# esp32.net
KiCad netlist of a schematic drawn in Altium Designer
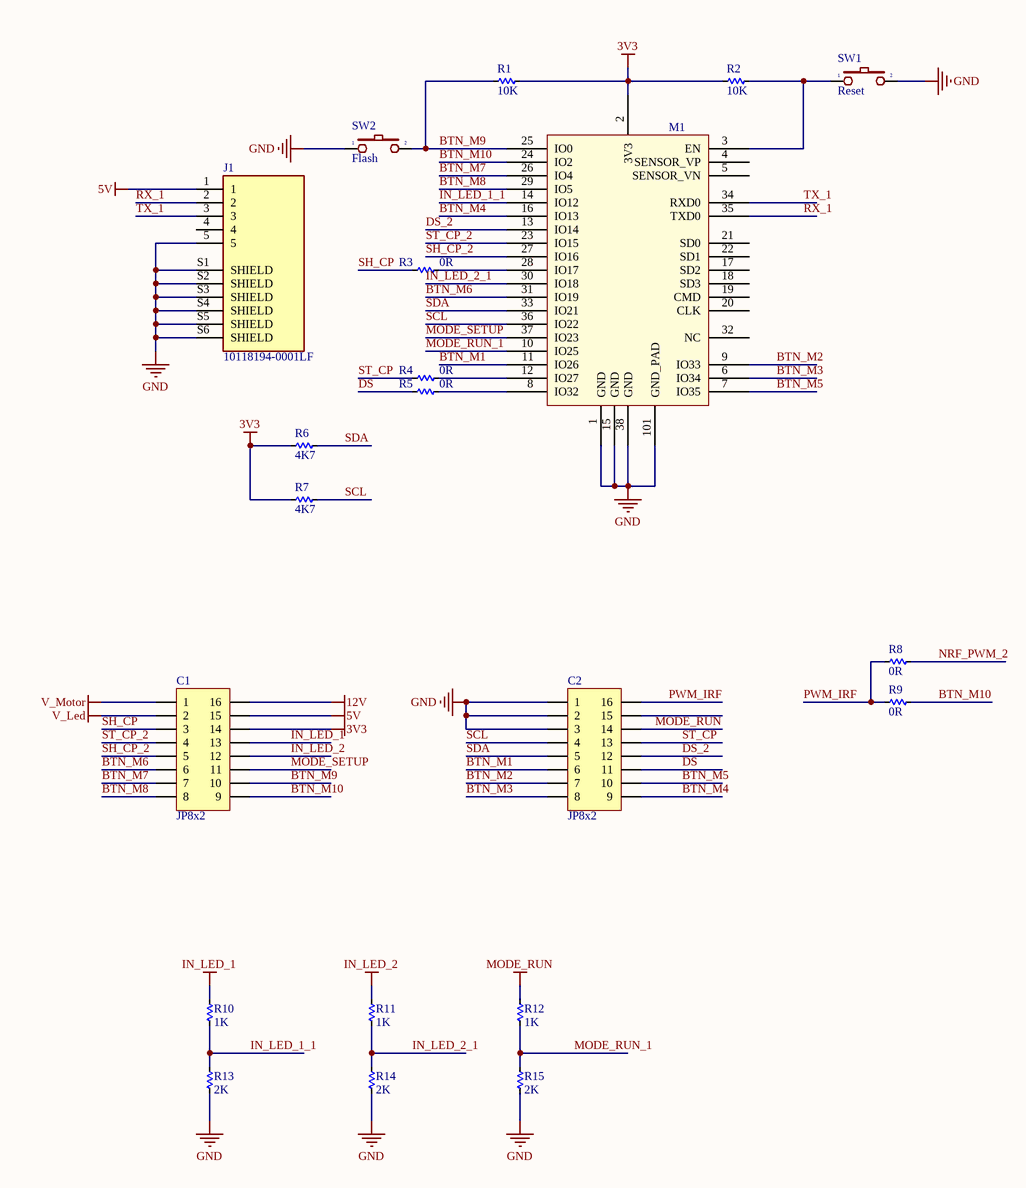
[diagram p0: esp32.SchDoc]

(export (version "E")
  (design (tool "Eeschema 10.0.6"))
  (components
    (comp (ref "C1")
      (value "JP8x2")
      (footprint "JP8-C2T")
      (description "WR-PHD 2.54 mm Dual Socket Header")
      (fields
        (field (name "MANUFACTURER") "Würth Elektronik eiSos GmbH")
        (field (name "PARTNO") "61301621821")
        (field (name "CREATED BY") "Karrer Zheng")
      )
      (libsource (lib "LIBRARY") (part "JP8x2"))
    )
    (comp (ref "C2")
      (value "JP8x2")
      (footprint "JP8-C2T")
      (description "WR-PHD 2.54 mm Dual Socket Header")
      (fields
        (field (name "MANUFACTURER") "Würth Elektronik eiSos GmbH")
        (field (name "PARTNO") "61301621821")
        (field (name "CREATED BY") "Karrer Zheng")
      )
      (libsource (lib "LIBRARY") (part "JP8x2"))
    )
    (comp (ref "J1")
      (value "10118194-0001LF")
      (footprint "AMPHENOL_10118194-0001LF")
      (description "USB - micro B USB 2.0 Receptacle Connector 5 Position Surface Mount, Right Angle; Through Hole")
      (fields (field (name "MF") "Amphenol ICC"))
      (libsource (lib "10118194-0001LF") (part "10118194-0001LF"))
    )
    (comp (ref "M1")
      (value "ESP32S_Module")
      (footprint "ESP32S")
      (description "Esp-32S")
      (libsource (lib "ESP32S") (part "ESP32S_Module"))
    )
    (comp (ref "R1")
      (value "10K")
      (footprint "RES-SMD-0603")
      (description "Resistor")
      (fields
        (field (name "MANUFACTURER") "Generic Components")
        (field (name "PUBLISHER") "Altium Hobart Technology Centre")
      )
      (libsource (lib "LIBRARY") (part "Res-SMD"))
    )
    (comp (ref "R2")
      (value "10K")
      (footprint "RES-SMD-0603")
      (description "Resistor")
      (fields
        (field (name "MANUFACTURER") "Generic Components")
        (field (name "PUBLISHER") "Altium Hobart Technology Centre")
      )
      (libsource (lib "LIBRARY") (part "Res-SMD"))
    )
    (comp (ref "R3")
      (value "0R")
      (footprint "RES-SMD-0603")
      (description "Resistor")
      (fields
        (field (name "MANUFACTURER") "Generic Components")
        (field (name "PUBLISHER") "Altium Hobart Technology Centre")
      )
      (libsource (lib "LIBRARY") (part "Res-SMD"))
    )
    (comp (ref "R4")
      (value "0R")
      (footprint "RES-SMD-0603")
      (description "Resistor")
      (fields
        (field (name "MANUFACTURER") "Generic Components")
        (field (name "PUBLISHER") "Altium Hobart Technology Centre")
      )
      (libsource (lib "LIBRARY") (part "Res-SMD"))
    )
    (comp (ref "R5")
      (value "0R")
      (footprint "RES-SMD-0603")
      (description "Resistor")
      (fields
        (field (name "MANUFACTURER") "Generic Components")
        (field (name "PUBLISHER") "Altium Hobart Technology Centre")
      )
      (libsource (lib "LIBRARY") (part "Res-SMD"))
    )
    (comp (ref "R6")
      (value "4K7")
      (footprint "RES-SMD-0603")
      (description "Resistor")
      (fields
        (field (name "MANUFACTURER") "Generic Components")
        (field (name "PUBLISHER") "Altium Hobart Technology Centre")
      )
      (libsource (lib "LIBRARY") (part "Res-SMD"))
    )
    (comp (ref "R7")
      (value "4K7")
      (footprint "RES-SMD-0603")
      (description "Resistor")
      (fields
        (field (name "MANUFACTURER") "Generic Components")
        (field (name "PUBLISHER") "Altium Hobart Technology Centre")
      )
      (libsource (lib "LIBRARY") (part "Res-SMD"))
    )
    (comp (ref "R8")
      (value "0R")
      (footprint "RES-SMD-0603")
      (description "Resistor")
      (fields
        (field (name "MANUFACTURER") "Generic Components")
        (field (name "PUBLISHER") "Altium Hobart Technology Centre")
      )
      (libsource (lib "LIBRARY") (part "Res-SMD"))
    )
    (comp (ref "R9")
      (value "0R")
      (footprint "RES-SMD-0603")
      (description "Resistor")
      (fields
        (field (name "MANUFACTURER") "Generic Components")
        (field (name "PUBLISHER") "Altium Hobart Technology Centre")
      )
      (libsource (lib "LIBRARY") (part "Res-SMD"))
    )
    (comp (ref "R10")
      (value "1K")
      (footprint "RES-SMD-0603")
      (description "Resistor")
      (fields
        (field (name "MANUFACTURER") "Generic Components")
        (field (name "PUBLISHER") "Altium Hobart Technology Centre")
      )
      (libsource (lib "LIBRARY") (part "Res-SMD"))
    )
    (comp (ref "R11")
      (value "1K")
      (footprint "RES-SMD-0603")
      (description "Resistor")
      (fields
        (field (name "MANUFACTURER") "Generic Components")
        (field (name "PUBLISHER") "Altium Hobart Technology Centre")
      )
      (libsource (lib "LIBRARY") (part "Res-SMD"))
    )
    (comp (ref "R12")
      (value "1K")
      (footprint "RES-SMD-0603")
      (description "Resistor")
      (fields
        (field (name "MANUFACTURER") "Generic Components")
        (field (name "PUBLISHER") "Altium Hobart Technology Centre")
      )
      (libsource (lib "LIBRARY") (part "Res-SMD"))
    )
    (comp (ref "R13")
      (value "2K")
      (footprint "RES-SMD-0603")
      (description "Resistor")
      (fields
        (field (name "MANUFACTURER") "Generic Components")
        (field (name "PUBLISHER") "Altium Hobart Technology Centre")
      )
      (libsource (lib "LIBRARY") (part "Res-SMD"))
    )
    (comp (ref "R14")
      (value "2K")
      (footprint "RES-SMD-0603")
      (description "Resistor")
      (fields
        (field (name "MANUFACTURER") "Generic Components")
        (field (name "PUBLISHER") "Altium Hobart Technology Centre")
      )
      (libsource (lib "LIBRARY") (part "Res-SMD"))
    )
    (comp (ref "R15")
      (value "2K")
      (footprint "RES-SMD-0603")
      (description "Resistor")
      (fields
        (field (name "MANUFACTURER") "Generic Components")
        (field (name "PUBLISHER") "Altium Hobart Technology Centre")
      )
      (libsource (lib "LIBRARY") (part "Res-SMD"))
    )
    (comp (ref "SW1")
      (value "Reset")
      (footprint "SW1-SMD")
      (description "Switch button 2 pin")
      (libsource (lib "LIBRARY") (part "SW2"))
    )
    (comp (ref "SW2")
      (value "Flash")
      (footprint "SW-DIP1-1")
      (description "Switch button 2 pin")
      (libsource (lib "LIBRARY") (part "SW2"))
    )
  )
  (nets
    (net (code "1") (name "/BTN_M1") (class "Default")
      (node (ref "C2") (pin "6") (pinfunction "6_6") (pintype "passive"))
      (node (ref "M1") (pin "11") (pinfunction "IO26_11") (pintype "passive"))
    )
    (net (code "2") (name "/BTN_M2") (class "Default")
      (node (ref "C2") (pin "7") (pinfunction "7_7") (pintype "passive"))
      (node (ref "M1") (pin "9") (pinfunction "IO33_9") (pintype "passive"))
    )
    (net (code "3") (name "/BTN_M3") (class "Default")
      (node (ref "C2") (pin "8") (pinfunction "8_8") (pintype "passive"))
      (node (ref "M1") (pin "6") (pinfunction "IO34_6") (pintype "passive"))
    )
    (net (code "4") (name "/BTN_M4") (class "Default")
      (node (ref "C2") (pin "9") (pinfunction "9_9") (pintype "passive"))
      (node (ref "M1") (pin "16") (pinfunction "IO13_16") (pintype "passive"))
    )
    (net (code "5") (name "/BTN_M5") (class "Default")
      (node (ref "C2") (pin "10") (pinfunction "10_10") (pintype "passive"))
      (node (ref "M1") (pin "7") (pinfunction "IO35_7") (pintype "passive"))
    )
    (net (code "6") (name "/BTN_M6") (class "Default")
      (node (ref "C1") (pin "6") (pinfunction "6_6") (pintype "passive"))
      (node (ref "M1") (pin "31") (pinfunction "IO19_31") (pintype "passive"))
    )
    (net (code "7") (name "/BTN_M7") (class "Default")
      (node (ref "C1") (pin "7") (pinfunction "7_7") (pintype "passive"))
      (node (ref "M1") (pin "26") (pinfunction "IO4_26") (pintype "passive"))
    )
    (net (code "8") (name "/BTN_M8") (class "Default")
      (node (ref "C1") (pin "8") (pinfunction "8_8") (pintype "passive"))
      (node (ref "M1") (pin "29") (pinfunction "IO5_29") (pintype "passive"))
    )
    (net (code "9") (name "/BTN_M9") (class "Default")
      (node (ref "C1") (pin "10") (pinfunction "10_10") (pintype "passive"))
      (node (ref "M1") (pin "25") (pinfunction "IO0_25") (pintype "passive"))
      (node (ref "R1") (pin "2") (pinfunction "2_2") (pintype "passive"))
      (node (ref "SW2") (pin "2") (pinfunction "2_2") (pintype "passive"))
    )
    (net (code "10") (name "/BTN_M10") (class "Default")
      (node (ref "C1") (pin "9") (pinfunction "9_9") (pintype "passive"))
      (node (ref "M1") (pin "24") (pinfunction "IO2_24") (pintype "passive"))
      (node (ref "R9") (pin "1") (pinfunction "1_1") (pintype "passive"))
    )
    (net (code "11") (name "/DS") (class "Default")
      (node (ref "C2") (pin "11") (pinfunction "11_11") (pintype "passive"))
      (node (ref "R5") (pin "1") (pinfunction "1_1") (pintype "passive"))
    )
    (net (code "12") (name "/DS_2") (class "Default")
      (node (ref "C2") (pin "12") (pinfunction "12_12") (pintype "passive"))
      (node (ref "M1") (pin "13") (pinfunction "IO14_13") (pintype "passive"))
    )
    (net (code "13") (name "/IN_LED_1_1") (class "Default")
      (node (ref "M1") (pin "14") (pinfunction "IO12_14") (pintype "passive"))
      (node (ref "R10") (pin "1") (pinfunction "1_1") (pintype "passive"))
      (node (ref "R13") (pin "2") (pinfunction "2_2") (pintype "passive"))
    )
    (net (code "14") (name "/IN_LED_2_1") (class "Default")
      (node (ref "M1") (pin "30") (pinfunction "IO18_30") (pintype "passive"))
      (node (ref "R11") (pin "1") (pinfunction "1_1") (pintype "passive"))
      (node (ref "R14") (pin "2") (pinfunction "2_2") (pintype "passive"))
    )
    (net (code "15") (name "/MODE_RUN_1") (class "Default")
      (node (ref "M1") (pin "10") (pinfunction "IO25_10") (pintype "passive"))
      (node (ref "R12") (pin "1") (pinfunction "1_1") (pintype "passive"))
      (node (ref "R15") (pin "2") (pinfunction "2_2") (pintype "passive"))
    )
    (net (code "16") (name "/MODE_SETUP") (class "Default")
      (node (ref "C1") (pin "11") (pinfunction "11_11") (pintype "passive"))
      (node (ref "M1") (pin "37") (pinfunction "IO23_37") (pintype "passive"))
    )
    (net (code "17") (name "/NRF_PWM_2") (class "Default")
      (node (ref "R8") (pin "1") (pinfunction "1_1") (pintype "passive"))
    )
    (net (code "18") (name "/PWM_IRF") (class "Default")
      (node (ref "C2") (pin "16") (pinfunction "16_16") (pintype "passive"))
      (node (ref "R8") (pin "2") (pinfunction "2_2") (pintype "passive"))
      (node (ref "R9") (pin "2") (pinfunction "2_2") (pintype "passive"))
    )
    (net (code "19") (name "/RX_1") (class "Default")
      (node (ref "J1") (pin "2") (pinfunction "2_2") (pintype "passive"))
      (node (ref "M1") (pin "35") (pinfunction "TXD0_35") (pintype "passive"))
    )
    (net (code "20") (name "/SCL") (class "Default")
      (node (ref "C2") (pin "4") (pinfunction "4_4") (pintype "passive"))
      (node (ref "M1") (pin "36") (pinfunction "IO22_36") (pintype "passive"))
      (node (ref "R7") (pin "2") (pinfunction "2_2") (pintype "passive"))
    )
    (net (code "21") (name "/SDA") (class "Default")
      (node (ref "C2") (pin "5") (pinfunction "5_5") (pintype "passive"))
      (node (ref "M1") (pin "33") (pinfunction "IO21_33") (pintype "passive"))
      (node (ref "R6") (pin "2") (pinfunction "2_2") (pintype "passive"))
    )
    (net (code "22") (name "/SH_CP") (class "Default")
      (node (ref "C1") (pin "3") (pinfunction "3_3") (pintype "passive"))
      (node (ref "R3") (pin "1") (pinfunction "1_1") (pintype "passive"))
    )
    (net (code "23") (name "/SH_CP_2") (class "Default")
      (node (ref "C1") (pin "5") (pinfunction "5_5") (pintype "passive"))
      (node (ref "M1") (pin "27") (pinfunction "IO16_27") (pintype "passive"))
    )
    (net (code "24") (name "/ST_CP") (class "Default")
      (node (ref "C2") (pin "13") (pinfunction "13_13") (pintype "passive"))
      (node (ref "R4") (pin "1") (pinfunction "1_1") (pintype "passive"))
    )
    (net (code "25") (name "/ST_CP_2") (class "Default")
      (node (ref "C1") (pin "4") (pinfunction "4_4") (pintype "passive"))
      (node (ref "M1") (pin "23") (pinfunction "IO15_23") (pintype "passive"))
    )
    (net (code "26") (name "/TX_1") (class "Default")
      (node (ref "J1") (pin "3") (pinfunction "3_3") (pintype "passive"))
      (node (ref "M1") (pin "34") (pinfunction "RXD0_34") (pintype "passive"))
    )
    (net (code "27") (name "3V3") (class "Default")
      (node (ref "C1") (pin "14") (pinfunction "14_14") (pintype "passive"))
      (node (ref "M1") (pin "2") (pinfunction "3V3_2") (pintype "power_in"))
      (node (ref "R1") (pin "1") (pinfunction "1_1") (pintype "passive"))
      (node (ref "R2") (pin "2") (pinfunction "2_2") (pintype "passive"))
      (node (ref "R6") (pin "1") (pinfunction "1_1") (pintype "passive"))
      (node (ref "R7") (pin "1") (pinfunction "1_1") (pintype "passive"))
    )
    (net (code "28") (name "5V") (class "Default")
      (node (ref "C1") (pin "15") (pinfunction "15_15") (pintype "passive"))
      (node (ref "J1") (pin "1") (pinfunction "1_1") (pintype "passive"))
    )
    (net (code "29") (name "12V") (class "Default")
      (node (ref "C1") (pin "16") (pinfunction "16_16") (pintype "passive"))
    )
    (net (code "30") (name "GND") (class "Default")
      (node (ref "C2") (pin "1") (pinfunction "1_1") (pintype "passive"))
      (node (ref "C2") (pin "2") (pinfunction "2_2") (pintype "passive"))
      (node (ref "C2") (pin "3") (pinfunction "3_3") (pintype "passive"))
      (node (ref "J1") (pin "5") (pinfunction "5_5") (pintype "passive"))
      (node (ref "J1") (pin "S1") (pinfunction "SHIELD_S1") (pintype "passive"))
      (node (ref "J1") (pin "S2") (pinfunction "SHIELD_S2") (pintype "passive"))
      (node (ref "J1") (pin "S3") (pinfunction "SHIELD_S3") (pintype "passive"))
      (node (ref "J1") (pin "S4") (pinfunction "SHIELD_S4") (pintype "passive"))
      (node (ref "J1") (pin "S5") (pinfunction "SHIELD_S5") (pintype "passive"))
      (node (ref "J1") (pin "S6") (pinfunction "SHIELD_S6") (pintype "passive"))
      (node (ref "M1") (pin "1") (pinfunction "GND_1") (pintype "power_in"))
      (node (ref "M1") (pin "101") (pinfunction "GND_PAD_101") (pintype "power_in"))
      (node (ref "M1") (pin "15") (pinfunction "GND_15") (pintype "power_in"))
      (node (ref "M1") (pin "38") (pinfunction "GND_38") (pintype "power_in"))
      (node (ref "R13") (pin "1") (pinfunction "1_1") (pintype "passive"))
      (node (ref "R14") (pin "1") (pinfunction "1_1") (pintype "passive"))
      (node (ref "R15") (pin "1") (pinfunction "1_1") (pintype "passive"))
      (node (ref "SW1") (pin "2") (pinfunction "2_2") (pintype "passive"))
      (node (ref "SW2") (pin "1") (pinfunction "1_1") (pintype "passive"))
    )
    (net (code "31") (name "IN_LED_1") (class "Default")
      (node (ref "C1") (pin "13") (pinfunction "13_13") (pintype "passive"))
      (node (ref "R10") (pin "2") (pinfunction "2_2") (pintype "passive"))
    )
    (net (code "32") (name "IN_LED_2") (class "Default")
      (node (ref "C1") (pin "12") (pinfunction "12_12") (pintype "passive"))
      (node (ref "R11") (pin "2") (pinfunction "2_2") (pintype "passive"))
    )
    (net (code "33") (name "MODE_RUN") (class "Default")
      (node (ref "C2") (pin "14") (pinfunction "14_14") (pintype "passive"))
      (node (ref "R12") (pin "2") (pinfunction "2_2") (pintype "passive"))
    )
    (net (code "34") (name "Net-(M1-EN)") (class "Default")
      (node (ref "M1") (pin "3") (pinfunction "EN_3") (pintype "power_in"))
      (node (ref "R2") (pin "1") (pinfunction "1_1") (pintype "passive"))
      (node (ref "SW1") (pin "1") (pinfunction "1_1") (pintype "passive"))
    )
    (net (code "35") (name "Net-(M1-IO17)") (class "Default")
      (node (ref "M1") (pin "28") (pinfunction "IO17_28") (pintype "passive"))
      (node (ref "R3") (pin "2") (pinfunction "2_2") (pintype "passive"))
    )
    (net (code "36") (name "Net-(M1-IO27)") (class "Default")
      (node (ref "M1") (pin "12") (pinfunction "IO27_12") (pintype "passive"))
      (node (ref "R4") (pin "2") (pinfunction "2_2") (pintype "passive"))
    )
    (net (code "37") (name "Net-(M1-IO32)") (class "Default")
      (node (ref "M1") (pin "8") (pinfunction "IO32_8") (pintype "passive"))
      (node (ref "R5") (pin "2") (pinfunction "2_2") (pintype "passive"))
    )
    (net (code "38") (name "V_Led") (class "Default")
      (node (ref "C1") (pin "2") (pinfunction "2_2") (pintype "passive"))
    )
    (net (code "39") (name "V_Motor") (class "Default")
      (node (ref "C1") (pin "1") (pinfunction "1_1") (pintype "passive"))
    )
    (net (code "40") (name "unconnected-(C2-Pad15)") (class "Default")
      (node (ref "C2") (pin "15") (pinfunction "15_15") (pintype "passive"))
    )
    (net (code "41") (name "unconnected-(J1-Pad4)") (class "Default")
      (node (ref "J1") (pin "4") (pinfunction "4_4") (pintype "passive"))
    )
    (net (code "42") (name "unconnected-(M1-CLK-Pad20)") (class "Default")
      (node (ref "M1") (pin "20") (pinfunction "CLK_20") (pintype "passive"))
    )
    (net (code "43") (name "unconnected-(M1-CMD-Pad19)") (class "Default")
      (node (ref "M1") (pin "19") (pinfunction "CMD_19") (pintype "passive"))
    )
    (net (code "44") (name "unconnected-(M1-NC-Pad32)") (class "Default")
      (node (ref "M1") (pin "32") (pinfunction "NC_32") (pintype "passive"))
    )
    (net (code "45") (name "unconnected-(M1-SD0-Pad21)") (class "Default")
      (node (ref "M1") (pin "21") (pinfunction "SD0_21") (pintype "passive"))
    )
    (net (code "46") (name "unconnected-(M1-SD1-Pad22)") (class "Default")
      (node (ref "M1") (pin "22") (pinfunction "SD1_22") (pintype "passive"))
    )
    (net (code "47") (name "unconnected-(M1-SD2-Pad17)") (class "Default")
      (node (ref "M1") (pin "17") (pinfunction "SD2_17") (pintype "passive"))
    )
    (net (code "48") (name "unconnected-(M1-SD3-Pad18)") (class "Default")
      (node (ref "M1") (pin "18") (pinfunction "SD3_18") (pintype "passive"))
    )
    (net (code "49") (name "unconnected-(M1-SENSOR_VN-Pad5)") (class "Default")
      (node (ref "M1") (pin "5") (pinfunction "SENSOR_VN_5") (pintype "passive"))
    )
    (net (code "50") (name "unconnected-(M1-SENSOR_VP-Pad4)") (class "Default")
      (node (ref "M1") (pin "4") (pinfunction "SENSOR_VP_4") (pintype "passive"))
    )
  )
)
